# magicBoard.net
KiCad netlist of a schematic drawn in EAGLE
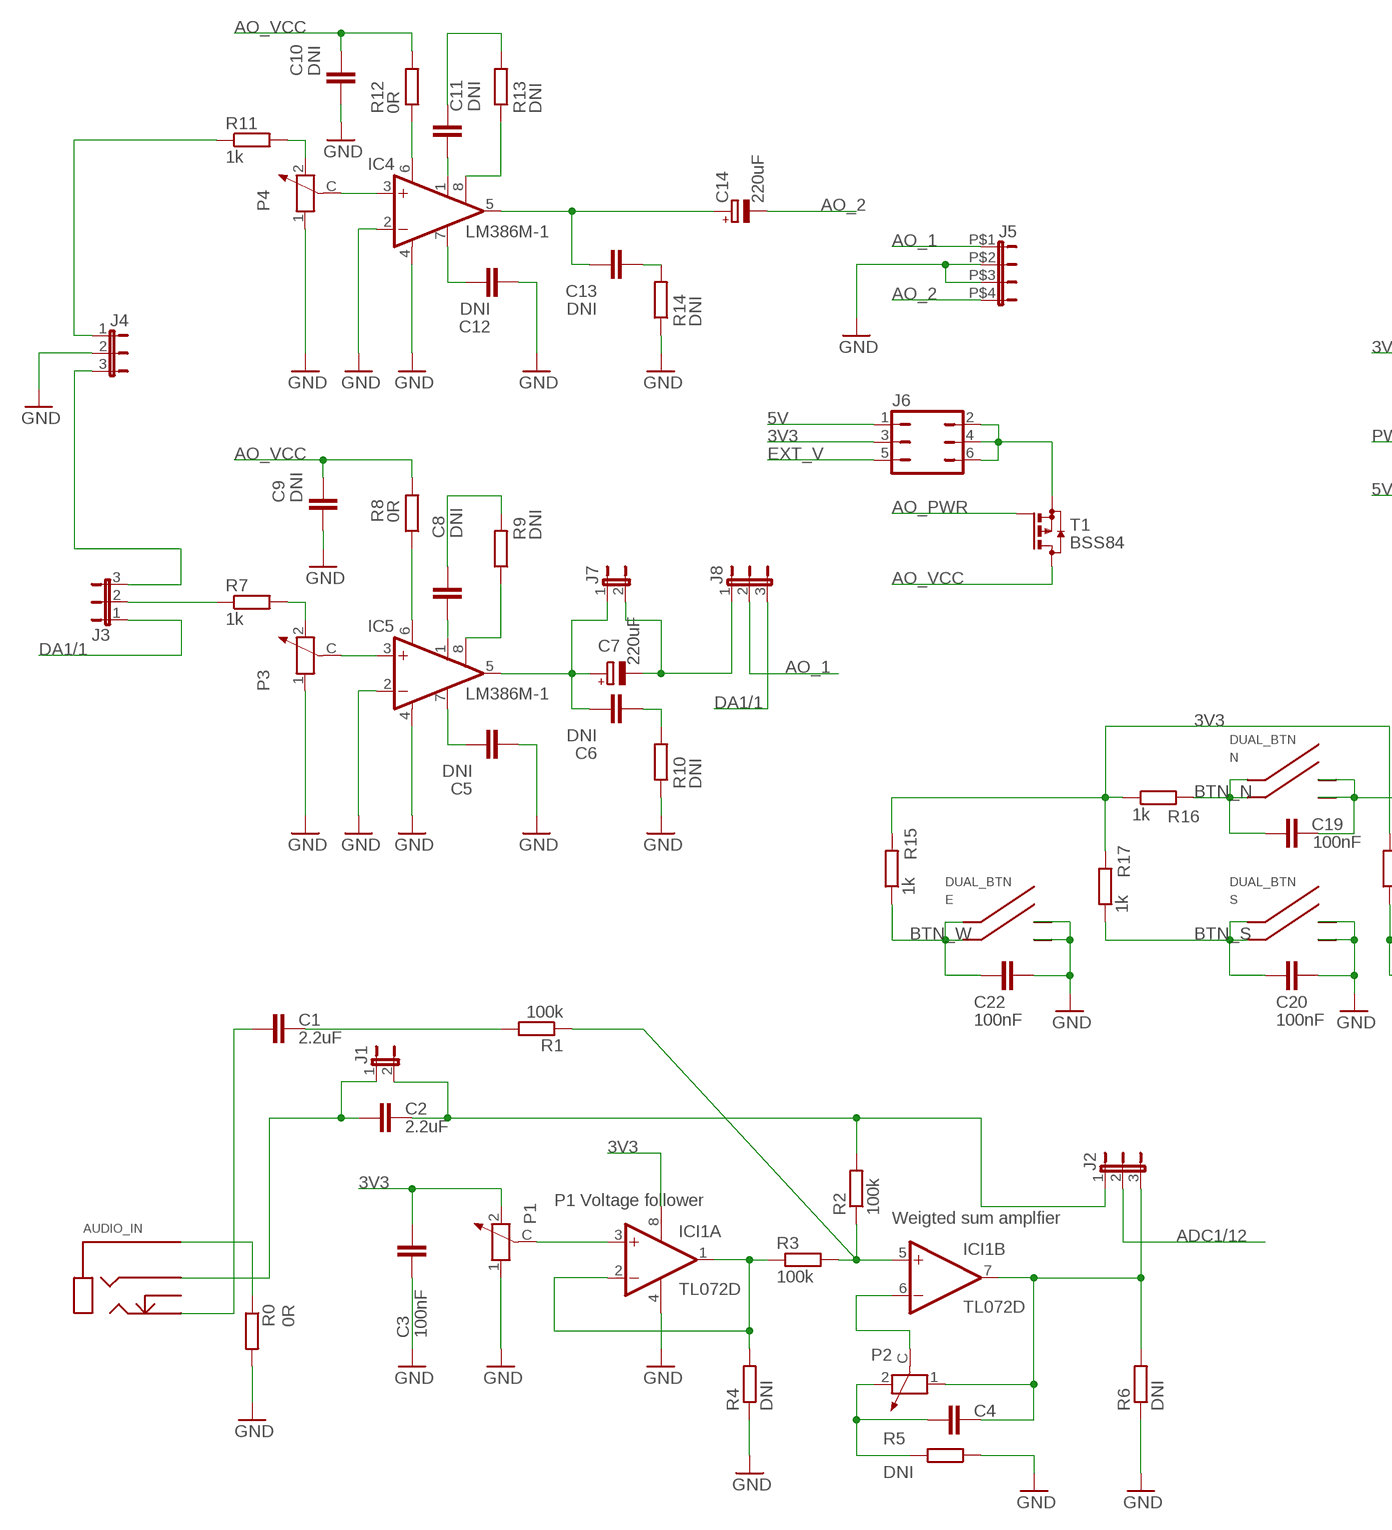
[diagram p0: schematic, sheet 1, part 1 of 2]
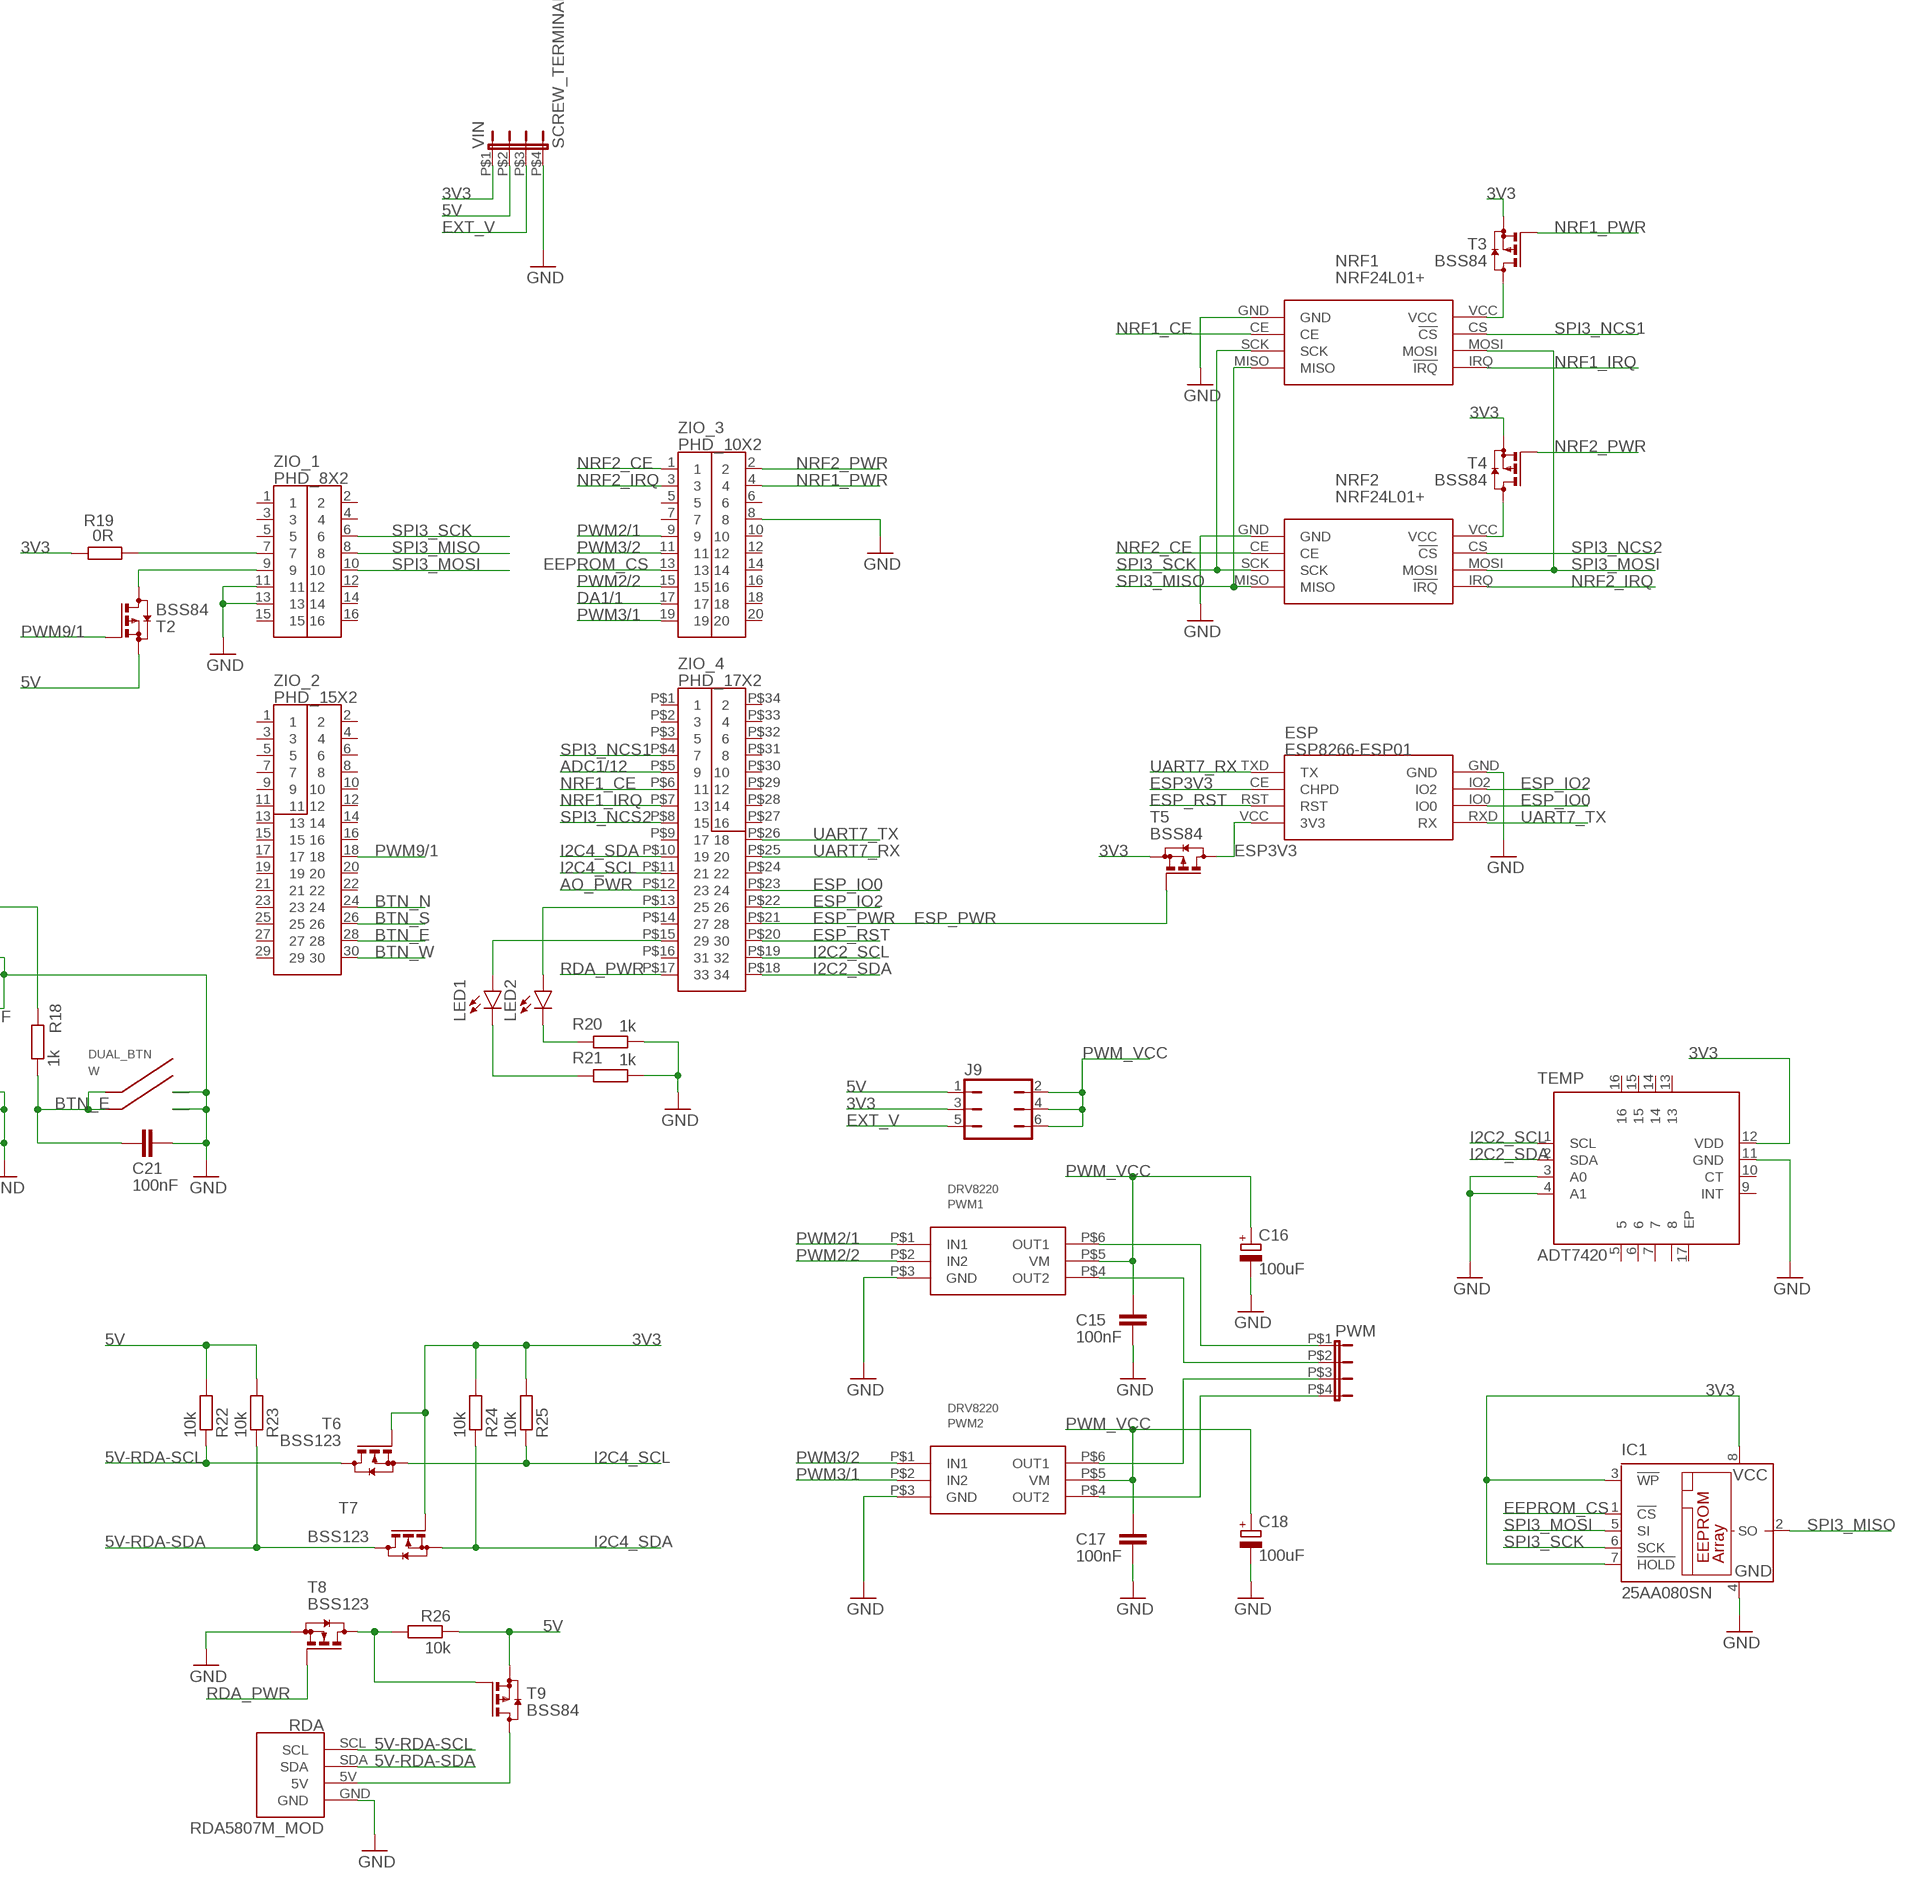
[diagram p1: schematic, sheet 1, part 2 of 2]

(export (version "E")
  (design (tool "Eeschema 10.0.6"))
  (components
    (comp (ref "AUDIO_IN")
      (value "CON_JACK")
      (footprint "eagle-import:CON_JACK")
      (libsource (lib "eagle-import") (part "CON_JACK"))
    )
    (comp (ref "C1")
      (value "2.2uF")
      (footprint "eagle-import:C0805")
      (libsource (lib "eagle-import") (part "C-EUC0805"))
    )
    (comp (ref "C2")
      (value "2.2uF")
      (footprint "eagle-import:C0805")
      (libsource (lib "eagle-import") (part "C-EUC0805"))
    )
    (comp (ref "C3")
      (value "100nF")
      (footprint "eagle-import:C0805")
      (libsource (lib "eagle-import") (part "C-EUC0805"))
    )
    (comp (ref "C4")
      (value "DNI")
      (footprint "eagle-import:C0805")
      (libsource (lib "eagle-import") (part "C-EUC0805"))
    )
    (comp (ref "C5")
      (value "DNI")
      (footprint "eagle-import:C0805")
      (libsource (lib "eagle-import") (part "C-EUC0805"))
    )
    (comp (ref "C6")
      (value "DNI")
      (footprint "eagle-import:C0805")
      (libsource (lib "eagle-import") (part "C-EUC0805"))
    )
    (comp (ref "C7")
      (value "220uF")
      (footprint "eagle-import:E2,5-6E")
      (libsource (lib "eagle-import") (part "CPOL-EUE2,5-6E"))
    )
    (comp (ref "C8")
      (value "DNI")
      (footprint "eagle-import:C0805")
      (libsource (lib "eagle-import") (part "C-EUC0805"))
    )
    (comp (ref "C9")
      (value "DNI")
      (footprint "eagle-import:C0805")
      (libsource (lib "eagle-import") (part "C-EUC0805"))
    )
    (comp (ref "C10")
      (value "DNI")
      (footprint "eagle-import:C0805")
      (libsource (lib "eagle-import") (part "C-EUC0805"))
    )
    (comp (ref "C11")
      (value "DNI")
      (footprint "eagle-import:C0805")
      (libsource (lib "eagle-import") (part "C-EUC0805"))
    )
    (comp (ref "C12")
      (value "DNI")
      (footprint "eagle-import:C0805")
      (libsource (lib "eagle-import") (part "C-EUC0805"))
    )
    (comp (ref "C13")
      (value "DNI")
      (footprint "eagle-import:C0805")
      (libsource (lib "eagle-import") (part "C-EUC0805"))
    )
    (comp (ref "C14")
      (value "220uF")
      (footprint "eagle-import:E2,5-6E")
      (libsource (lib "eagle-import") (part "CPOL-EUE2,5-6E"))
    )
    (comp (ref "C15")
      (value "100nF")
      (footprint "eagle-import:C0805")
      (libsource (lib "eagle-import") (part "C-EUC0805"))
    )
    (comp (ref "C16")
      (value "100uF")
      (footprint "eagle-import:E2,5-6E")
      (libsource (lib "eagle-import") (part "CPOL-EUE2,5-6E"))
    )
    (comp (ref "C17")
      (value "100nF")
      (footprint "eagle-import:C0805")
      (libsource (lib "eagle-import") (part "C-EUC0805"))
    )
    (comp (ref "C18")
      (value "100uF")
      (footprint "eagle-import:E2,5-6E")
      (libsource (lib "eagle-import") (part "CPOL-EUE2,5-6E"))
    )
    (comp (ref "C19")
      (value "100nF")
      (footprint "eagle-import:C0805")
      (libsource (lib "eagle-import") (part "C-EUC0805"))
    )
    (comp (ref "C20")
      (value "100nF")
      (footprint "eagle-import:C0805")
      (libsource (lib "eagle-import") (part "C-EUC0805"))
    )
    (comp (ref "C21")
      (value "100nF")
      (footprint "eagle-import:C0805")
      (libsource (lib "eagle-import") (part "C-EUC0805"))
    )
    (comp (ref "C22")
      (value "100nF")
      (footprint "eagle-import:C0805")
      (libsource (lib "eagle-import") (part "C-EUC0805"))
    )
    (comp (ref "E")
      (value "DUAL_BTN")
      (footprint "eagle-import:SMT_BTN")
      (libsource (lib "eagle-import") (part "DUAL_BTN"))
    )
    (comp (ref "ESP")
      (value "ESP8266-ESP01")
      (footprint "eagle-import:ESP8266-ESP01")
      (libsource (lib "eagle-import") (part "ESP8266-ESP01"))
    )
    (comp (ref "IC1")
      (value "25AA080SN")
      (footprint "eagle-import:SO-08")
      (fields (field (name "MF") "MICROCHIP") (field (name "MPN") "25AA080/SN"))
      (libsource (lib "eagle-import") (part "25SNAA080"))
    )
    (comp (ref "IC4")
      (value "LM386M-1")
      (footprint "eagle-import:SO08")
      (libsource (lib "eagle-import") (part "LM386?-M1"))
    )
    (comp (ref "IC5")
      (value "LM386M-1")
      (footprint "eagle-import:SO08")
      (libsource (lib "eagle-import") (part "LM386?-M1"))
    )
    (comp (ref "ICI1")
      (value "TL072D")
      (footprint "eagle-import:SO08")
      (libsource (lib "eagle-import") (part "TL072D"))
    )
    (comp (ref "J1")
      (value "JP1E")
      (footprint "eagle-import:JP1")
      (libsource (lib "eagle-import") (part "JP1E"))
    )
    (comp (ref "J2")
      (value "JP2E")
      (footprint "eagle-import:JP2")
      (libsource (lib "eagle-import") (part "JP2E"))
    )
    (comp (ref "J3")
      (value "JP2E")
      (footprint "eagle-import:JP2")
      (libsource (lib "eagle-import") (part "JP2E"))
    )
    (comp (ref "J4")
      (value "JP2E")
      (footprint "eagle-import:JP2")
      (libsource (lib "eagle-import") (part "JP2E"))
    )
    (comp (ref "J5")
      (value "SCREW_TERMINAL")
      (footprint "eagle-import:SCREW_TERMINAL")
      (libsource (lib "eagle-import") (part "SCREW_TERMINAL"))
    )
    (comp (ref "J6")
      (value "JP3Q")
      (footprint "eagle-import:JP3Q")
      (libsource (lib "eagle-import") (part "JP3Q"))
    )
    (comp (ref "J7")
      (value "JP1E")
      (footprint "eagle-import:JP1")
      (libsource (lib "eagle-import") (part "JP1E"))
    )
    (comp (ref "J8")
      (value "JP2E")
      (footprint "eagle-import:JP2")
      (libsource (lib "eagle-import") (part "JP2E"))
    )
    (comp (ref "J9")
      (value "JP3Q")
      (footprint "eagle-import:JP3Q")
      (libsource (lib "eagle-import") (part "JP3Q"))
    )
    (comp (ref "LED1")
      (value "LEDSMT1206")
      (footprint "eagle-import:1206")
      (libsource (lib "eagle-import") (part "LEDSMT1206"))
    )
    (comp (ref "LED2")
      (value "LEDSMT1206")
      (footprint "eagle-import:1206")
      (libsource (lib "eagle-import") (part "LEDSMT1206"))
    )
    (comp (ref "N")
      (value "DUAL_BTN")
      (footprint "eagle-import:SMT_BTN")
      (libsource (lib "eagle-import") (part "DUAL_BTN"))
    )
    (comp (ref "NRF1")
      (value "NRF24L01+")
      (footprint "eagle-import:NRF24L01+")
      (libsource (lib "eagle-import") (part "NRF24L01+"))
    )
    (comp (ref "NRF2")
      (value "NRF24L01+")
      (footprint "eagle-import:NRF24L01+")
      (libsource (lib "eagle-import") (part "NRF24L01+"))
    )
    (comp (ref "P1")
      (value "35W-POT")
      (footprint "eagle-import:35W_POT")
      (libsource (lib "eagle-import") (part "35W-POT"))
    )
    (comp (ref "P2")
      (value "35W-POT")
      (footprint "eagle-import:35W_POT")
      (libsource (lib "eagle-import") (part "35W-POT"))
    )
    (comp (ref "P3")
      (value "35W-POT")
      (footprint "eagle-import:35W_POT")
      (libsource (lib "eagle-import") (part "35W-POT"))
    )
    (comp (ref "P4")
      (value "35W-POT")
      (footprint "eagle-import:35W_POT")
      (libsource (lib "eagle-import") (part "35W-POT"))
    )
    (comp (ref "PWM")
      (value "SCREW_TERMINAL")
      (footprint "eagle-import:SCREW_TERMINAL")
      (libsource (lib "eagle-import") (part "SCREW_TERMINAL"))
    )
    (comp (ref "PWM1")
      (value "DRV8220")
      (footprint "eagle-import:SOT-5X3")
      (libsource (lib "eagle-import") (part "DRV8220"))
    )
    (comp (ref "PWM2")
      (value "DRV8220")
      (footprint "eagle-import:SOT-5X3")
      (libsource (lib "eagle-import") (part "DRV8220"))
    )
    (comp (ref "R0")
      (value "0R")
      (footprint "eagle-import:R0805")
      (libsource (lib "eagle-import") (part "R-EU_R0805"))
    )
    (comp (ref "R1")
      (value "100k")
      (footprint "eagle-import:R0805")
      (libsource (lib "eagle-import") (part "R-EU_R0805"))
    )
    (comp (ref "R2")
      (value "100k")
      (footprint "eagle-import:R0805")
      (libsource (lib "eagle-import") (part "R-EU_R0805"))
    )
    (comp (ref "R3")
      (value "100k")
      (footprint "eagle-import:R0805")
      (libsource (lib "eagle-import") (part "R-EU_R0805"))
    )
    (comp (ref "R4")
      (value "DNI")
      (footprint "eagle-import:R0805")
      (libsource (lib "eagle-import") (part "R-EU_R0805"))
    )
    (comp (ref "R5")
      (value "DNI")
      (footprint "eagle-import:R0805")
      (libsource (lib "eagle-import") (part "R-EU_R0805"))
    )
    (comp (ref "R6")
      (value "DNI")
      (footprint "eagle-import:R0805")
      (libsource (lib "eagle-import") (part "R-EU_R0805"))
    )
    (comp (ref "R7")
      (value "1k")
      (footprint "eagle-import:R0805")
      (libsource (lib "eagle-import") (part "R-EU_R0805"))
    )
    (comp (ref "R8")
      (value "0R")
      (footprint "eagle-import:R0805")
      (libsource (lib "eagle-import") (part "R-EU_R0805"))
    )
    (comp (ref "R9")
      (value "DNI")
      (footprint "eagle-import:R0805")
      (libsource (lib "eagle-import") (part "R-EU_R0805"))
    )
    (comp (ref "R10")
      (value "DNI")
      (footprint "eagle-import:R0805")
      (libsource (lib "eagle-import") (part "R-EU_R0805"))
    )
    (comp (ref "R11")
      (value "1k")
      (footprint "eagle-import:R0805")
      (libsource (lib "eagle-import") (part "R-EU_R0805"))
    )
    (comp (ref "R12")
      (value "0R")
      (footprint "eagle-import:R0805")
      (libsource (lib "eagle-import") (part "R-EU_R0805"))
    )
    (comp (ref "R13")
      (value "DNI")
      (footprint "eagle-import:R0805")
      (libsource (lib "eagle-import") (part "R-EU_R0805"))
    )
    (comp (ref "R14")
      (value "DNI")
      (footprint "eagle-import:R0805")
      (libsource (lib "eagle-import") (part "R-EU_R0805"))
    )
    (comp (ref "R15")
      (value "1k")
      (footprint "eagle-import:R0805")
      (libsource (lib "eagle-import") (part "R-EU_R0805"))
    )
    (comp (ref "R16")
      (value "1k")
      (footprint "eagle-import:R0805")
      (libsource (lib "eagle-import") (part "R-EU_R0805"))
    )
    (comp (ref "R17")
      (value "1k")
      (footprint "eagle-import:R0805")
      (libsource (lib "eagle-import") (part "R-EU_R0805"))
    )
    (comp (ref "R18")
      (value "1k")
      (footprint "eagle-import:R0805")
      (libsource (lib "eagle-import") (part "R-EU_R0805"))
    )
    (comp (ref "R19")
      (value "0R")
      (footprint "eagle-import:R0805")
      (libsource (lib "eagle-import") (part "R-EU_R0805"))
    )
    (comp (ref "R20")
      (value "1k")
      (footprint "eagle-import:R0805")
      (libsource (lib "eagle-import") (part "R-EU_R0805"))
    )
    (comp (ref "R21")
      (value "1k")
      (footprint "eagle-import:R0805")
      (libsource (lib "eagle-import") (part "R-EU_R0805"))
    )
    (comp (ref "R22")
      (value "10k")
      (footprint "eagle-import:R0805")
      (libsource (lib "eagle-import") (part "R-EU_R0805"))
    )
    (comp (ref "R23")
      (value "10k")
      (footprint "eagle-import:R0805")
      (libsource (lib "eagle-import") (part "R-EU_R0805"))
    )
    (comp (ref "R24")
      (value "10k")
      (footprint "eagle-import:R0805")
      (libsource (lib "eagle-import") (part "R-EU_R0805"))
    )
    (comp (ref "R25")
      (value "10k")
      (footprint "eagle-import:R0805")
      (libsource (lib "eagle-import") (part "R-EU_R0805"))
    )
    (comp (ref "R26")
      (value "10k")
      (footprint "eagle-import:R0805")
      (libsource (lib "eagle-import") (part "R-EU_R0805"))
    )
    (comp (ref "RDA")
      (value "RDA5807M_MOD")
      (footprint "eagle-import:RDA5807M")
      (libsource (lib "eagle-import") (part "RDA5807M_MOD"))
    )
    (comp (ref "S")
      (value "DUAL_BTN")
      (footprint "eagle-import:SMT_BTN")
      (libsource (lib "eagle-import") (part "DUAL_BTN"))
    )
    (comp (ref "T1")
      (value "BSS84")
      (footprint "eagle-import:SOT23")
      (libsource (lib "eagle-import") (part "BSS84"))
    )
    (comp (ref "T2")
      (value "BSS84")
      (footprint "eagle-import:SOT23")
      (libsource (lib "eagle-import") (part "BSS84"))
    )
    (comp (ref "T3")
      (value "BSS84")
      (footprint "eagle-import:SOT23")
      (libsource (lib "eagle-import") (part "BSS84"))
    )
    (comp (ref "T4")
      (value "BSS84")
      (footprint "eagle-import:SOT23")
      (libsource (lib "eagle-import") (part "BSS84"))
    )
    (comp (ref "T5")
      (value "BSS84")
      (footprint "eagle-import:SOT23")
      (libsource (lib "eagle-import") (part "BSS84"))
    )
    (comp (ref "T6")
      (value "BSS123")
      (footprint "eagle-import:SOT23")
      (libsource (lib "eagle-import") (part "BSS123"))
    )
    (comp (ref "T7")
      (value "BSS123")
      (footprint "eagle-import:SOT23")
      (libsource (lib "eagle-import") (part "BSS123"))
    )
    (comp (ref "T8")
      (value "BSS123")
      (footprint "eagle-import:SOT23")
      (libsource (lib "eagle-import") (part "BSS123"))
    )
    (comp (ref "T9")
      (value "BSS84")
      (footprint "eagle-import:SOT23")
      (libsource (lib "eagle-import") (part "BSS84"))
    )
    (comp (ref "TEMP")
      (value "ADT7420")
      (footprint "eagle-import:LFCSP-16")
      (libsource (lib "eagle-import") (part "ADT7420"))
    )
    (comp (ref "VIN")
      (value "SCREW_TERMINAL")
      (footprint "eagle-import:SCREW_TERMINAL")
      (libsource (lib "eagle-import") (part "SCREW_TERMINAL"))
    )
    (comp (ref "W")
      (value "DUAL_BTN")
      (footprint "eagle-import:SMT_BTN")
      (libsource (lib "eagle-import") (part "DUAL_BTN"))
    )
    (comp (ref "ZIO_1")
      (value "PHD_8X2")
      (footprint "eagle-import:PHD_8X2")
      (libsource (lib "eagle-import") (part "PHD_8X2"))
    )
    (comp (ref "ZIO_2")
      (value "PHD_15X2")
      (footprint "eagle-import:PHD_15X2")
      (libsource (lib "eagle-import") (part "PHD_15X2"))
    )
    (comp (ref "ZIO_3")
      (value "PHD_10X2")
      (footprint "eagle-import:PHD_10X2")
      (libsource (lib "eagle-import") (part "PHD_10X2"))
    )
    (comp (ref "ZIO_4")
      (value "PHD_17X2")
      (footprint "eagle-import:PHD_17X2")
      (libsource (lib "eagle-import") (part "PHD_17X2"))
    )
  )
  (nets
    (net (code "1") (name "/3V3") (class "Default")
      (node (ref "C3") (pin "1") (pinfunction "1_1") (pintype "passive"))
      (node (ref "IC1") (pin "3") (pinfunction "~{WP}_3") (pintype "input"))
      (node (ref "IC1") (pin "7") (pinfunction "~{HOLD}_7") (pintype "input"))
      (node (ref "IC1") (pin "8") (pinfunction "VCC_8") (pintype "power_in"))
      (node (ref "ICI1") (pin "8") (pinfunction "V+_8") (pintype "power_in"))
      (node (ref "J6") (pin "3") (pinfunction "3_3") (pintype "passive"))
      (node (ref "J9") (pin "3") (pinfunction "3_3") (pintype "passive"))
      (node (ref "P1") (pin "2") (pinfunction "2_2") (pintype "passive"))
      (node (ref "R15") (pin "2") (pinfunction "2_2") (pintype "passive"))
      (node (ref "R16") (pin "1") (pinfunction "1_1") (pintype "passive"))
      (node (ref "R17") (pin "2") (pinfunction "2_2") (pintype "passive"))
      (node (ref "R18") (pin "2") (pinfunction "2_2") (pintype "passive"))
      (node (ref "R19") (pin "2") (pinfunction "2_2") (pintype "passive"))
      (node (ref "R24") (pin "2") (pinfunction "2_2") (pintype "passive"))
      (node (ref "R25") (pin "2") (pinfunction "2_2") (pintype "passive"))
      (node (ref "T3") (pin "2") (pinfunction "S_2") (pintype "passive"))
      (node (ref "T4") (pin "2") (pinfunction "S_2") (pintype "passive"))
      (node (ref "T5") (pin "2") (pinfunction "S_2") (pintype "passive"))
      (node (ref "T6") (pin "1") (pinfunction "G_1") (pintype "passive"))
      (node (ref "T7") (pin "1") (pinfunction "G_1") (pintype "passive"))
      (node (ref "TEMP") (pin "12") (pinfunction "VDD_12") (pintype "input"))
      (node (ref "VIN") (pin "P$1") (pinfunction "1_P$1") (pintype "passive"))
    )
    (net (code "2") (name "/5V") (class "Default")
      (node (ref "J6") (pin "1") (pinfunction "1_1") (pintype "passive"))
      (node (ref "J9") (pin "1") (pinfunction "1_1") (pintype "passive"))
      (node (ref "R22") (pin "2") (pinfunction "2_2") (pintype "passive"))
      (node (ref "R23") (pin "2") (pinfunction "2_2") (pintype "passive"))
      (node (ref "R26") (pin "1") (pinfunction "1_1") (pintype "passive"))
      (node (ref "T2") (pin "2") (pinfunction "S_2") (pintype "passive"))
      (node (ref "T9") (pin "2") (pinfunction "S_2") (pintype "passive"))
      (node (ref "VIN") (pin "P$2") (pinfunction "2_P$2") (pintype "passive"))
    )
    (net (code "3") (name "/5V-RDA-SCL") (class "Default")
      (node (ref "R22") (pin "1") (pinfunction "1_1") (pintype "passive"))
      (node (ref "RDA") (pin "SCL") (pinfunction "SCL_SCL") (pintype "bidirectional"))
      (node (ref "T6") (pin "3") (pinfunction "D_3") (pintype "passive"))
    )
    (net (code "4") (name "/5V-RDA-SDA") (class "Default")
      (node (ref "R23") (pin "1") (pinfunction "1_1") (pintype "passive"))
      (node (ref "RDA") (pin "SDA") (pinfunction "SDA_SDA") (pintype "bidirectional"))
      (node (ref "T7") (pin "3") (pinfunction "D_3") (pintype "passive"))
    )
    (net (code "5") (name "/ADC1{slash}12") (class "Default")
      (node (ref "J2") (pin "2") (pinfunction "2_2") (pintype "passive"))
      (node (ref "ZIO_4") (pin "P$5") (pinfunction "9_P$5") (pintype "bidirectional"))
    )
    (net (code "6") (name "/AO_1") (class "Default")
      (node (ref "J5") (pin "P$1") (pinfunction "1_P$1") (pintype "passive"))
      (node (ref "J8") (pin "2") (pinfunction "2_2") (pintype "passive"))
    )
    (net (code "7") (name "/AO_2") (class "Default")
      (node (ref "C14") (pin "-") (pinfunction "-_-") (pintype "passive"))
      (node (ref "J5") (pin "P$4") (pinfunction "4_P$4") (pintype "passive"))
    )
    (net (code "8") (name "/AO_PWR") (class "Default")
      (node (ref "T1") (pin "1") (pinfunction "G_1") (pintype "passive"))
      (node (ref "ZIO_4") (pin "P$12") (pinfunction "23_P$12") (pintype "bidirectional"))
    )
    (net (code "9") (name "/AO_VCC") (class "Default")
      (node (ref "C10") (pin "1") (pinfunction "1_1") (pintype "passive"))
      (node (ref "C9") (pin "1") (pinfunction "1_1") (pintype "passive"))
      (node (ref "R12") (pin "2") (pinfunction "2_2") (pintype "passive"))
      (node (ref "R8") (pin "2") (pinfunction "2_2") (pintype "passive"))
      (node (ref "T1") (pin "3") (pinfunction "D_3") (pintype "passive"))
    )
    (net (code "10") (name "/BTN_E") (class "Default")
      (node (ref "C21") (pin "1") (pinfunction "1_1") (pintype "passive"))
      (node (ref "R18") (pin "1") (pinfunction "1_1") (pintype "passive"))
      (node (ref "W") (pin "H1") (pinfunction "L1_H1") (pintype "bidirectional"))
      (node (ref "W") (pin "H2") (pinfunction "L2_H2") (pintype "bidirectional"))
      (node (ref "ZIO_2") (pin "28") (pinfunction "28_28") (pintype "bidirectional"))
    )
    (net (code "11") (name "/BTN_N") (class "Default")
      (node (ref "C19") (pin "1") (pinfunction "1_1") (pintype "passive"))
      (node (ref "N") (pin "H1") (pinfunction "L1_H1") (pintype "bidirectional"))
      (node (ref "N") (pin "H2") (pinfunction "L2_H2") (pintype "bidirectional"))
      (node (ref "R16") (pin "2") (pinfunction "2_2") (pintype "passive"))
      (node (ref "ZIO_2") (pin "24") (pinfunction "24_24") (pintype "bidirectional"))
    )
    (net (code "12") (name "/BTN_S") (class "Default")
      (node (ref "C20") (pin "1") (pinfunction "1_1") (pintype "passive"))
      (node (ref "R17") (pin "1") (pinfunction "1_1") (pintype "passive"))
      (node (ref "S") (pin "H1") (pinfunction "L1_H1") (pintype "bidirectional"))
      (node (ref "S") (pin "H2") (pinfunction "L2_H2") (pintype "bidirectional"))
      (node (ref "ZIO_2") (pin "26") (pinfunction "26_26") (pintype "bidirectional"))
    )
    (net (code "13") (name "/BTN_W") (class "Default")
      (node (ref "C22") (pin "1") (pinfunction "1_1") (pintype "passive"))
      (node (ref "E") (pin "H1") (pinfunction "L1_H1") (pintype "bidirectional"))
      (node (ref "E") (pin "H2") (pinfunction "L2_H2") (pintype "bidirectional"))
      (node (ref "R15") (pin "1") (pinfunction "1_1") (pintype "passive"))
      (node (ref "ZIO_2") (pin "30") (pinfunction "30_30") (pintype "bidirectional"))
    )
    (net (code "14") (name "/DA1{slash}1") (class "Default")
      (node (ref "J3") (pin "1") (pinfunction "1_1") (pintype "passive"))
      (node (ref "J8") (pin "3") (pinfunction "3_3") (pintype "passive"))
      (node (ref "ZIO_3") (pin "17") (pinfunction "17_17") (pintype "bidirectional"))
    )
    (net (code "15") (name "/EEPROM_CS") (class "Default")
      (node (ref "IC1") (pin "1") (pinfunction "~{CS}_1") (pintype "input"))
      (node (ref "ZIO_3") (pin "13") (pinfunction "13_13") (pintype "bidirectional"))
    )
    (net (code "16") (name "/ESP3V3") (class "Default")
      (node (ref "ESP") (pin "CE") (pinfunction "CHPD_CE") (pintype "bidirectional"))
      (node (ref "ESP") (pin "VCC") (pinfunction "3V3_VCC") (pintype "bidirectional"))
      (node (ref "T5") (pin "3") (pinfunction "D_3") (pintype "passive"))
    )
    (net (code "17") (name "/ESP_IO0") (class "Default")
      (node (ref "ESP") (pin "IO0") (pinfunction "IO0_IO0") (pintype "bidirectional"))
      (node (ref "ZIO_4") (pin "P$23") (pinfunction "24_P$23") (pintype "bidirectional"))
    )
    (net (code "18") (name "/ESP_IO2") (class "Default")
      (node (ref "ESP") (pin "IO2") (pinfunction "IO2_IO2") (pintype "bidirectional"))
      (node (ref "ZIO_4") (pin "P$22") (pinfunction "26_P$22") (pintype "bidirectional"))
    )
    (net (code "19") (name "/ESP_PWR") (class "Default")
      (node (ref "T5") (pin "1") (pinfunction "G_1") (pintype "passive"))
      (node (ref "ZIO_4") (pin "P$21") (pinfunction "28_P$21") (pintype "bidirectional"))
    )
    (net (code "20") (name "/ESP_RST") (class "Default")
      (node (ref "ESP") (pin "RST") (pinfunction "RST_RST") (pintype "bidirectional"))
      (node (ref "ZIO_4") (pin "P$20") (pinfunction "30_P$20") (pintype "bidirectional"))
    )
    (net (code "21") (name "/EXT_V") (class "Default")
      (node (ref "J6") (pin "5") (pinfunction "5_5") (pintype "passive"))
      (node (ref "J9") (pin "5") (pinfunction "5_5") (pintype "passive"))
      (node (ref "VIN") (pin "P$3") (pinfunction "3_P$3") (pintype "passive"))
    )
    (net (code "22") (name "/I2C2_SCL") (class "Default")
      (node (ref "TEMP") (pin "1") (pinfunction "SCL_1") (pintype "input"))
      (node (ref "ZIO_4") (pin "P$19") (pinfunction "32_P$19") (pintype "bidirectional"))
    )
    (net (code "23") (name "/I2C2_SDA") (class "Default")
      (node (ref "TEMP") (pin "2") (pinfunction "SDA_2") (pintype "input"))
      (node (ref "ZIO_4") (pin "P$18") (pinfunction "34_P$18") (pintype "bidirectional"))
    )
    (net (code "24") (name "/I2C4_SCL") (class "Default")
      (node (ref "R25") (pin "1") (pinfunction "1_1") (pintype "passive"))
      (node (ref "T6") (pin "2") (pinfunction "S_2") (pintype "passive"))
      (node (ref "ZIO_4") (pin "P$11") (pinfunction "21_P$11") (pintype "bidirectional"))
    )
    (net (code "25") (name "/I2C4_SDA") (class "Default")
      (node (ref "R24") (pin "1") (pinfunction "1_1") (pintype "passive"))
      (node (ref "T7") (pin "2") (pinfunction "S_2") (pintype "passive"))
      (node (ref "ZIO_4") (pin "P$10") (pinfunction "19_P$10") (pintype "bidirectional"))
    )
    (net (code "26") (name "/NRF1_CE") (class "Default")
      (node (ref "NRF1") (pin "CE") (pinfunction "CE_CE") (pintype "bidirectional"))
      (node (ref "ZIO_4") (pin "P$6") (pinfunction "11_P$6") (pintype "bidirectional"))
    )
    (net (code "27") (name "/NRF1_IRQ") (class "Default")
      (node (ref "NRF1") (pin "IRQ") (pinfunction "~{IRQ}_IRQ") (pintype "bidirectional"))
      (node (ref "ZIO_4") (pin "P$7") (pinfunction "13_P$7") (pintype "bidirectional"))
    )
    (net (code "28") (name "/NRF1_PWR") (class "Default")
      (node (ref "T3") (pin "1") (pinfunction "G_1") (pintype "passive"))
      (node (ref "ZIO_3") (pin "4") (pinfunction "4_4") (pintype "bidirectional"))
    )
    (net (code "29") (name "/NRF2_CE") (class "Default")
      (node (ref "NRF2") (pin "CE") (pinfunction "CE_CE") (pintype "bidirectional"))
      (node (ref "ZIO_3") (pin "1") (pinfunction "1_1") (pintype "bidirectional"))
    )
    (net (code "30") (name "/NRF2_IRQ") (class "Default")
      (node (ref "NRF2") (pin "IRQ") (pinfunction "~{IRQ}_IRQ") (pintype "bidirectional"))
      (node (ref "ZIO_3") (pin "3") (pinfunction "3_3") (pintype "bidirectional"))
    )
    (net (code "31") (name "/NRF2_PWR") (class "Default")
      (node (ref "T4") (pin "1") (pinfunction "G_1") (pintype "passive"))
      (node (ref "ZIO_3") (pin "2") (pinfunction "2_2") (pintype "bidirectional"))
    )
    (net (code "32") (name "/PWM2{slash}1") (class "Default")
      (node (ref "PWM1") (pin "P$1") (pinfunction "IN1_P$1") (pintype "bidirectional"))
      (node (ref "ZIO_3") (pin "9") (pinfunction "9_9") (pintype "bidirectional"))
    )
    (net (code "33") (name "/PWM2{slash}2") (class "Default")
      (node (ref "PWM1") (pin "P$2") (pinfunction "IN2_P$2") (pintype "bidirectional"))
      (node (ref "ZIO_3") (pin "15") (pinfunction "15_15") (pintype "bidirectional"))
    )
    (net (code "34") (name "/PWM3{slash}1") (class "Default")
      (node (ref "PWM2") (pin "P$2") (pinfunction "IN2_P$2") (pintype "bidirectional"))
      (node (ref "ZIO_3") (pin "19") (pinfunction "19_19") (pintype "bidirectional"))
    )
    (net (code "35") (name "/PWM3{slash}2") (class "Default")
      (node (ref "PWM2") (pin "P$1") (pinfunction "IN1_P$1") (pintype "bidirectional"))
      (node (ref "ZIO_3") (pin "11") (pinfunction "11_11") (pintype "bidirectional"))
    )
    (net (code "36") (name "/PWM9{slash}1") (class "Default")
      (node (ref "T2") (pin "1") (pinfunction "G_1") (pintype "passive"))
      (node (ref "ZIO_2") (pin "18") (pinfunction "18_18") (pintype "bidirectional"))
    )
    (net (code "37") (name "/PWM_VCC") (class "Default")
      (node (ref "C15") (pin "1") (pinfunction "1_1") (pintype "passive"))
      (node (ref "C16") (pin "+") (pinfunction "+_+") (pintype "passive"))
      (node (ref "C17") (pin "1") (pinfunction "1_1") (pintype "passive"))
      (node (ref "C18") (pin "+") (pinfunction "+_+") (pintype "passive"))
      (node (ref "J9") (pin "2") (pinfunction "2_2") (pintype "passive"))
      (node (ref "J9") (pin "4") (pinfunction "4_4") (pintype "passive"))
      (node (ref "J9") (pin "6") (pinfunction "6_6") (pintype "passive"))
      (node (ref "PWM1") (pin "P$5") (pinfunction "VM_P$5") (pintype "bidirectional"))
      (node (ref "PWM2") (pin "P$5") (pinfunction "VM_P$5") (pintype "bidirectional"))
    )
    (net (code "38") (name "/RDA_PWR") (class "Default")
      (node (ref "T8") (pin "1") (pinfunction "G_1") (pintype "passive"))
      (node (ref "ZIO_4") (pin "P$17") (pinfunction "33_P$17") (pintype "bidirectional"))
    )
    (net (code "39") (name "/SPI3_MISO") (class "Default")
      (node (ref "IC1") (pin "2") (pinfunction "SO_2") (pintype "bidirectional"))
      (node (ref "NRF1") (pin "MISO") (pinfunction "MISO_MISO") (pintype "bidirectional"))
      (node (ref "NRF2") (pin "MISO") (pinfunction "MISO_MISO") (pintype "bidirectional"))
      (node (ref "ZIO_1") (pin "8") (pinfunction "8_8") (pintype "bidirectional"))
    )
    (net (code "40") (name "/SPI3_MOSI") (class "Default")
      (node (ref "IC1") (pin "5") (pinfunction "SI_5") (pintype "input"))
      (node (ref "NRF1") (pin "MOSI") (pinfunction "MOSI_MOSI") (pintype "bidirectional"))
      (node (ref "NRF2") (pin "MOSI") (pinfunction "MOSI_MOSI") (pintype "bidirectional"))
      (node (ref "ZIO_1") (pin "10") (pinfunction "10_10") (pintype "bidirectional"))
    )
    (net (code "41") (name "/SPI3_NCS1") (class "Default")
      (node (ref "NRF1") (pin "CS") (pinfunction "~{CS}_CS") (pintype "bidirectional"))
      (node (ref "ZIO_4") (pin "P$4") (pinfunction "7_P$4") (pintype "bidirectional"))
    )
    (net (code "42") (name "/SPI3_NCS2") (class "Default")
      (node (ref "NRF2") (pin "CS") (pinfunction "~{CS}_CS") (pintype "bidirectional"))
      (node (ref "ZIO_4") (pin "P$8") (pinfunction "15_P$8") (pintype "bidirectional"))
    )
    (net (code "43") (name "/SPI3_SCK") (class "Default")
      (node (ref "IC1") (pin "6") (pinfunction "SCK_6") (pintype "input"))
      (node (ref "NRF1") (pin "SCK") (pinfunction "SCK_SCK") (pintype "bidirectional"))
      (node (ref "NRF2") (pin "SCK") (pinfunction "SCK_SCK") (pintype "bidirectional"))
      (node (ref "ZIO_1") (pin "6") (pinfunction "6_6") (pintype "bidirectional"))
    )
    (net (code "44") (name "/UART7_RX") (class "Default")
      (node (ref "ESP") (pin "TXD") (pinfunction "TX_TXD") (pintype "bidirectional"))
      (node (ref "ZIO_4") (pin "P$25") (pinfunction "20_P$25") (pintype "bidirectional"))
    )
    (net (code "45") (name "/UART7_TX") (class "Default")
      (node (ref "ESP") (pin "RXD") (pinfunction "RX_RXD") (pintype "bidirectional"))
      (node (ref "ZIO_4") (pin "P$26") (pinfunction "18_P$26") (pintype "bidirectional"))
    )
    (net (code "46") (name "GND") (class "Default")
      (node (ref "C10") (pin "2") (pinfunction "2_2") (pintype "passive"))
      (node (ref "C12") (pin "2") (pinfunction "2_2") (pintype "passive"))
      (node (ref "C15") (pin "2") (pinfunction "2_2") (pintype "passive"))
      (node (ref "C16") (pin "-") (pinfunction "-_-") (pintype "passive"))
      (node (ref "C17") (pin "2") (pinfunction "2_2") (pintype "passive"))
      (node (ref "C18") (pin "-") (pinfunction "-_-") (pintype "passive"))
      (node (ref "C19") (pin "2") (pinfunction "2_2") (pintype "passive"))
      (node (ref "C20") (pin "2") (pinfunction "2_2") (pintype "passive"))
      (node (ref "C21") (pin "2") (pinfunction "2_2") (pintype "passive"))
      (node (ref "C22") (pin "2") (pinfunction "2_2") (pintype "passive"))
      (node (ref "C3") (pin "2") (pinfunction "2_2") (pintype "passive"))
      (node (ref "C5") (pin "2") (pinfunction "2_2") (pintype "passive"))
      (node (ref "C9") (pin "2") (pinfunction "2_2") (pintype "passive"))
      (node (ref "E") (pin "L1") (pinfunction "R1_L1") (pintype "bidirectional"))
      (node (ref "E") (pin "L2") (pinfunction "R2_L2") (pintype "bidirectional"))
      (node (ref "ESP") (pin "GND") (pinfunction "GND_GND") (pintype "bidirectional"))
      (node (ref "IC1") (pin "4") (pinfunction "GND_4") (pintype "power_in"))
      (node (ref "IC4") (pin "2") (pinfunction "-IN_2") (pintype "input"))
      (node (ref "IC4") (pin "4") (pinfunction "GND_4") (pintype "power_in"))
      (node (ref "IC5") (pin "2") (pinfunction "-IN_2") (pintype "input"))
      (node (ref "IC5") (pin "4") (pinfunction "GND_4") (pintype "power_in"))
      (node (ref "ICI1") (pin "4") (pinfunction "V-_4") (pintype "power_in"))
      (node (ref "J4") (pin "2") (pinfunction "2_2") (pintype "passive"))
      (node (ref "J5") (pin "P$2") (pinfunction "2_P$2") (pintype "passive"))
      (node (ref "J5") (pin "P$3") (pinfunction "3_P$3") (pintype "passive"))
      (node (ref "N") (pin "L1") (pinfunction "R1_L1") (pintype "bidirectional"))
      (node (ref "N") (pin "L2") (pinfunction "R2_L2") (pintype "bidirectional"))
      (node (ref "NRF1") (pin "GND") (pinfunction "GND_GND") (pintype "bidirectional"))
      (node (ref "NRF2") (pin "GND") (pinfunction "GND_GND") (pintype "bidirectional"))
      (node (ref "P1") (pin "1") (pinfunction "1_1") (pintype "passive"))
      (node (ref "P3") (pin "1") (pinfunction "1_1") (pintype "passive"))
      (node (ref "P4") (pin "1") (pinfunction "1_1") (pintype "passive"))
      (node (ref "PWM1") (pin "P$3") (pinfunction "GND_P$3") (pintype "bidirectional"))
      (node (ref "PWM2") (pin "P$3") (pinfunction "GND_P$3") (pintype "bidirectional"))
      (node (ref "R0") (pin "2") (pinfunction "2_2") (pintype "passive"))
      (node (ref "R10") (pin "1") (pinfunction "1_1") (pintype "passive"))
      (node (ref "R14") (pin "1") (pinfunction "1_1") (pintype "passive"))
      (node (ref "R20") (pin "1") (pinfunction "1_1") (pintype "passive"))
      (node (ref "R21") (pin "1") (pinfunction "1_1") (pintype "passive"))
      (node (ref "R4") (pin "1") (pinfunction "1_1") (pintype "passive"))
      (node (ref "R5") (pin "1") (pinfunction "1_1") (pintype "passive"))
      (node (ref "R6") (pin "1") (pinfunction "1_1") (pintype "passive"))
      (node (ref "RDA") (pin "GND") (pinfunction "GND_GND") (pintype "bidirectional"))
      (node (ref "S") (pin "L1") (pinfunction "R1_L1") (pintype "bidirectional"))
      (node (ref "S") (pin "L2") (pinfunction "R2_L2") (pintype "bidirectional"))
      (node (ref "T8") (pin "2") (pinfunction "S_2") (pintype "passive"))
      (node (ref "TEMP") (pin "11") (pinfunction "GND_11") (pintype "input"))
      (node (ref "TEMP") (pin "3") (pinfunction "A0_3") (pintype "input"))
      (node (ref "TEMP") (pin "4") (pinfunction "A1_4") (pintype "input"))
      (node (ref "VIN") (pin "P$4") (pinfunction "4_P$4") (pintype "passive"))
      (node (ref "W") (pin "L1") (pinfunction "R1_L1") (pintype "bidirectional"))
      (node (ref "W") (pin "L2") (pinfunction "R2_L2") (pintype "bidirectional"))
      (node (ref "ZIO_1") (pin "11") (pinfunction "11_11") (pintype "bidirectional"))
      (node (ref "ZIO_1") (pin "13") (pinfunction "13_13") (pintype "bidirectional"))
      (node (ref "ZIO_3") (pin "8") (pinfunction "8_8") (pintype "bidirectional"))
    )
    (net (code "47") (name "Net-(AUDIO_IN-3)") (class "Default")
      (node (ref "AUDIO_IN") (pin "2") (pinfunction "3_2") (pintype "bidirectional"))
      (node (ref "C2") (pin "2") (pinfunction "2_2") (pintype "passive"))
      (node (ref "J1") (pin "1") (pinfunction "1_1") (pintype "passive"))
    )
    (net (code "48") (name "Net-(AUDIO_IN-5)") (class "Default")
      (node (ref "AUDIO_IN") (pin "4") (pinfunction "5_4") (pintype "bidirectional"))
      (node (ref "C1") (pin "2") (pinfunction "2_2") (pintype "passive"))
    )
    (net (code "49") (name "Net-(AUDIO_IN-Pad1)") (class "Default")
      (node (ref "AUDIO_IN") (pin "1") (pinfunction "1_1") (pintype "bidirectional"))
      (node (ref "R0") (pin "1") (pinfunction "1_1") (pintype "passive"))
    )
    (net (code "50") (name "Net-(C1-Pad1)") (class "Default")
      (node (ref "C1") (pin "1") (pinfunction "1_1") (pintype "passive"))
      (node (ref "R1") (pin "2") (pinfunction "2_2") (pintype "passive"))
    )
    (net (code "51") (name "Net-(C2-Pad1)") (class "Default")
      (node (ref "C2") (pin "1") (pinfunction "1_1") (pintype "passive"))
      (node (ref "J1") (pin "2") (pinfunction "2_2") (pintype "passive"))
      (node (ref "J2") (pin "1") (pinfunction "1_1") (pintype "passive"))
      (node (ref "R2") (pin "2") (pinfunction "2_2") (pintype "passive"))
    )
    (net (code "52") (name "Net-(C4-Pad2)") (class "Default")
      (node (ref "C4") (pin "2") (pinfunction "2_2") (pintype "passive"))
      (node (ref "P2") (pin "2") (pinfunction "2_2") (pintype "passive"))
      (node (ref "R5") (pin "2") (pinfunction "2_2") (pintype "passive"))
    )
    (net (code "53") (name "Net-(C6-Pad2)") (class "Default")
      (node (ref "C6") (pin "2") (pinfunction "2_2") (pintype "passive"))
      (node (ref "R10") (pin "2") (pinfunction "2_2") (pintype "passive"))
    )
    (net (code "54") (name "Net-(C7-Pad-)") (class "Default")
      (node (ref "C7") (pin "-") (pinfunction "-_-") (pintype "passive"))
      (node (ref "J7") (pin "2") (pinfunction "2_2") (pintype "passive"))
      (node (ref "J8") (pin "1") (pinfunction "1_1") (pintype "passive"))
    )
    (net (code "55") (name "Net-(C8-Pad1)") (class "Default")
      (node (ref "C8") (pin "1") (pinfunction "1_1") (pintype "passive"))
      (node (ref "R9") (pin "2") (pinfunction "2_2") (pintype "passive"))
    )
    (net (code "56") (name "Net-(C8-Pad2)") (class "Default")
      (node (ref "C8") (pin "2") (pinfunction "2_2") (pintype "passive"))
      (node (ref "IC5") (pin "1") (pinfunction "GAIN_1") (pintype "passive"))
    )
    (net (code "57") (name "Net-(C11-Pad1)") (class "Default")
      (node (ref "C11") (pin "1") (pinfunction "1_1") (pintype "passive"))
      (node (ref "R13") (pin "2") (pinfunction "2_2") (pintype "passive"))
    )
    (net (code "58") (name "Net-(C11-Pad2)") (class "Default")
      (node (ref "C11") (pin "2") (pinfunction "2_2") (pintype "passive"))
      (node (ref "IC4") (pin "1") (pinfunction "GAIN_1") (pintype "passive"))
    )
    (net (code "59") (name "Net-(C13-Pad2)") (class "Default")
      (node (ref "C13") (pin "2") (pinfunction "2_2") (pintype "passive"))
      (node (ref "R14") (pin "2") (pinfunction "2_2") (pintype "passive"))
    )
    (net (code "60") (name "Net-(IC4-+IN)") (class "Default")
      (node (ref "IC4") (pin "3") (pinfunction "+IN_3") (pintype "input"))
      (node (ref "P4") (pin "C") (pinfunction "3_C") (pintype "passive"))
    )
    (net (code "61") (name "Net-(IC4-BYPASS)") (class "Default")
      (node (ref "C12") (pin "1") (pinfunction "1_1") (pintype "passive"))
      (node (ref "IC4") (pin "7") (pinfunction "BYPASS_7") (pintype "passive"))
    )
    (net (code "62") (name "Net-(IC4-GAIN-Pad8)") (class "Default")
      (node (ref "IC4") (pin "8") (pinfunction "GAIN_8") (pintype "passive"))
      (node (ref "R13") (pin "1") (pinfunction "1_1") (pintype "passive"))
    )
    (net (code "63") (name "Net-(IC4-OUT)") (class "Default")
      (node (ref "C13") (pin "1") (pinfunction "1_1") (pintype "passive"))
      (node (ref "C14") (pin "+") (pinfunction "+_+") (pintype "passive"))
      (node (ref "IC4") (pin "5") (pinfunction "OUT_5") (pintype "output"))
    )
    (net (code "64") (name "Net-(IC4-VS)") (class "Default")
      (node (ref "IC4") (pin "6") (pinfunction "VS_6") (pintype "power_in"))
      (node (ref "R12") (pin "1") (pinfunction "1_1") (pintype "passive"))
    )
    (net (code "65") (name "Net-(IC5-+IN)") (class "Default")
      (node (ref "IC5") (pin "3") (pinfunction "+IN_3") (pintype "input"))
      (node (ref "P3") (pin "C") (pinfunction "3_C") (pintype "passive"))
    )
    (net (code "66") (name "Net-(IC5-BYPASS)") (class "Default")
      (node (ref "C5") (pin "1") (pinfunction "1_1") (pintype "passive"))
      (node (ref "IC5") (pin "7") (pinfunction "BYPASS_7") (pintype "passive"))
    )
    (net (code "67") (name "Net-(IC5-GAIN-Pad8)") (class "Default")
      (node (ref "IC5") (pin "8") (pinfunction "GAIN_8") (pintype "passive"))
      (node (ref "R9") (pin "1") (pinfunction "1_1") (pintype "passive"))
    )
    (net (code "68") (name "Net-(IC5-OUT)") (class "Default")
      (node (ref "C6") (pin "1") (pinfunction "1_1") (pintype "passive"))
      (node (ref "C7") (pin "+") (pinfunction "+_+") (pintype "passive"))
      (node (ref "IC5") (pin "5") (pinfunction "OUT_5") (pintype "output"))
      (node (ref "J7") (pin "1") (pinfunction "1_1") (pintype "passive"))
    )
    (net (code "69") (name "Net-(IC5-VS)") (class "Default")
      (node (ref "IC5") (pin "6") (pinfunction "VS_6") (pintype "power_in"))
      (node (ref "R8") (pin "1") (pinfunction "1_1") (pintype "passive"))
    )
    (net (code "70") (name "Net-(ICI1A-+IN)") (class "Default")
      (node (ref "ICI1") (pin "3") (pinfunction "+IN_3") (pintype "input"))
      (node (ref "P1") (pin "C") (pinfunction "3_C") (pintype "passive"))
    )
    (net (code "71") (name "Net-(ICI1A--IN)") (class "Default")
      (node (ref "ICI1") (pin "1") (pinfunction "OUT_1") (pintype "output"))
      (node (ref "ICI1") (pin "2") (pinfunction "-IN_2") (pintype "input"))
      (node (ref "R3") (pin "1") (pinfunction "1_1") (pintype "passive"))
      (node (ref "R4") (pin "2") (pinfunction "2_2") (pintype "passive"))
    )
    (net (code "72") (name "Net-(ICI1B-+IN)") (class "Default")
      (node (ref "ICI1") (pin "5") (pinfunction "+IN_5") (pintype "input"))
      (node (ref "R1") (pin "1") (pinfunction "1_1") (pintype "passive"))
      (node (ref "R2") (pin "1") (pinfunction "1_1") (pintype "passive"))
      (node (ref "R3") (pin "2") (pinfunction "2_2") (pintype "passive"))
    )
    (net (code "73") (name "Net-(ICI1B--IN)") (class "Default")
      (node (ref "ICI1") (pin "6") (pinfunction "-IN_6") (pintype "input"))
      (node (ref "P2") (pin "C") (pinfunction "3_C") (pintype "passive"))
    )
    (net (code "74") (name "Net-(ICI1B-OUT)") (class "Default")
      (node (ref "C4") (pin "1") (pinfunction "1_1") (pintype "passive"))
      (node (ref "ICI1") (pin "7") (pinfunction "OUT_7") (pintype "output"))
      (node (ref "J2") (pin "3") (pinfunction "3_3") (pintype "passive"))
      (node (ref "P2") (pin "1") (pinfunction "1_1") (pintype "passive"))
      (node (ref "R6") (pin "2") (pinfunction "2_2") (pintype "passive"))
    )
    (net (code "75") (name "Net-(J3-Pad2)") (class "Default")
      (node (ref "J3") (pin "2") (pinfunction "2_2") (pintype "passive"))
      (node (ref "R7") (pin "1") (pinfunction "1_1") (pintype "passive"))
    )
    (net (code "76") (name "Net-(J3-Pad3)") (class "Default")
      (node (ref "J3") (pin "3") (pinfunction "3_3") (pintype "passive"))
      (node (ref "J4") (pin "3") (pinfunction "3_3") (pintype "passive"))
    )
    (net (code "77") (name "Net-(J4-Pad1)") (class "Default")
      (node (ref "J4") (pin "1") (pinfunction "1_1") (pintype "passive"))
      (node (ref "R11") (pin "1") (pinfunction "1_1") (pintype "passive"))
    )
    (net (code "78") (name "Net-(LED1-PadC)") (class "Default")
      (node (ref "LED1") (pin "C") (pinfunction "C_C") (pintype "passive"))
      (node (ref "R21") (pin "2") (pinfunction "2_2") (pintype "passive"))
    )
    (net (code "79") (name "Net-(LED2-PadC)") (class "Default")
      (node (ref "LED2") (pin "C") (pinfunction "C_C") (pintype "passive"))
      (node (ref "R20") (pin "2") (pinfunction "2_2") (pintype "passive"))
    )
    (net (code "80") (name "Net-(P3-Pad2)") (class "Default")
      (node (ref "P3") (pin "2") (pinfunction "2_2") (pintype "passive"))
      (node (ref "R7") (pin "2") (pinfunction "2_2") (pintype "passive"))
    )
    (net (code "81") (name "Net-(P4-Pad2)") (class "Default")
      (node (ref "P4") (pin "2") (pinfunction "2_2") (pintype "passive"))
      (node (ref "R11") (pin "2") (pinfunction "2_2") (pintype "passive"))
    )
    (net (code "82") (name "Net-(PWM-1)") (class "Default")
      (node (ref "PWM") (pin "P$1") (pinfunction "1_P$1") (pintype "passive"))
      (node (ref "PWM1") (pin "P$6") (pinfunction "OUT1_P$6") (pintype "bidirectional"))
    )
    (net (code "83") (name "Net-(PWM-2)") (class "Default")
      (node (ref "PWM") (pin "P$2") (pinfunction "2_P$2") (pintype "passive"))
      (node (ref "PWM1") (pin "P$4") (pinfunction "OUT2_P$4") (pintype "bidirectional"))
    )
    (net (code "84") (name "Net-(PWM-3)") (class "Default")
      (node (ref "PWM") (pin "P$3") (pinfunction "3_P$3") (pintype "passive"))
      (node (ref "PWM2") (pin "P$6") (pinfunction "OUT1_P$6") (pintype "bidirectional"))
    )
    (net (code "85") (name "Net-(PWM-4)") (class "Default")
      (node (ref "PWM") (pin "P$4") (pinfunction "4_P$4") (pintype "passive"))
      (node (ref "PWM2") (pin "P$4") (pinfunction "OUT2_P$4") (pintype "bidirectional"))
    )
    (net (code "86") (name "Net-(R19-Pad1)") (class "Default")
      (node (ref "R19") (pin "1") (pinfunction "1_1") (pintype "passive"))
      (node (ref "ZIO_1") (pin "7") (pinfunction "7_7") (pintype "bidirectional"))
    )
    (net (code "87") (name "Net-(T1-S)") (class "Default")
      (node (ref "J6") (pin "2") (pinfunction "2_2") (pintype "passive"))
      (node (ref "J6") (pin "4") (pinfunction "4_4") (pintype "passive"))
      (node (ref "J6") (pin "6") (pinfunction "6_6") (pintype "passive"))
      (node (ref "T1") (pin "2") (pinfunction "S_2") (pintype "passive"))
    )
    (net (code "88") (name "Net-(T2-D)") (class "Default")
      (node (ref "T2") (pin "3") (pinfunction "D_3") (pintype "passive"))
      (node (ref "ZIO_1") (pin "9") (pinfunction "9_9") (pintype "bidirectional"))
    )
    (net (code "89") (name "Net-(T3-D)") (class "Default")
      (node (ref "NRF1") (pin "VCC") (pinfunction "VCC_VCC") (pintype "bidirectional"))
      (node (ref "T3") (pin "3") (pinfunction "D_3") (pintype "passive"))
    )
    (net (code "90") (name "Net-(T4-D)") (class "Default")
      (node (ref "NRF2") (pin "VCC") (pinfunction "VCC_VCC") (pintype "bidirectional"))
      (node (ref "T4") (pin "3") (pinfunction "D_3") (pintype "passive"))
    )
    (net (code "91") (name "Net-(T8-D)") (class "Default")
      (node (ref "R26") (pin "2") (pinfunction "2_2") (pintype "passive"))
      (node (ref "T8") (pin "3") (pinfunction "D_3") (pintype "passive"))
      (node (ref "T9") (pin "1") (pinfunction "G_1") (pintype "passive"))
    )
    (net (code "92") (name "Net-(T9-D)") (class "Default")
      (node (ref "RDA") (pin "5V") (pinfunction "5V_5V") (pintype "bidirectional"))
      (node (ref "T9") (pin "3") (pinfunction "D_3") (pintype "passive"))
    )
    (net (code "93") (name "Net-(ZIO_4-25)") (class "Default")
      (node (ref "LED2") (pin "A") (pinfunction "A_A") (pintype "passive"))
      (node (ref "ZIO_4") (pin "P$13") (pinfunction "25_P$13") (pintype "bidirectional"))
    )
    (net (code "94") (name "Net-(ZIO_4-29)") (class "Default")
      (node (ref "LED1") (pin "A") (pinfunction "A_A") (pintype "passive"))
      (node (ref "ZIO_4") (pin "P$15") (pinfunction "29_P$15") (pintype "bidirectional"))
    )
    (net (code "95") (name "unconnected-(AUDIO_IN-4-Pad3)") (class "Default")
      (node (ref "AUDIO_IN") (pin "3") (pinfunction "4_3") (pintype "bidirectional"))
    )
    (net (code "96") (name "unconnected-(TEMP-CT-Pad10)") (class "Default")
      (node (ref "TEMP") (pin "10") (pinfunction "CT_10") (pintype "input"))
    )
    (net (code "97") (name "unconnected-(TEMP-EP-Pad17)") (class "Default")
      (node (ref "TEMP") (pin "17") (pinfunction "EP_17") (pintype "input"))
    )
    (net (code "98") (name "unconnected-(TEMP-INT-Pad9)") (class "Default")
      (node (ref "TEMP") (pin "9") (pinfunction "INT_9") (pintype "input"))
    )
    (net (code "99") (name "unconnected-(TEMP-Pad5)") (class "Default")
      (node (ref "TEMP") (pin "5") (pinfunction "5_5") (pintype "input"))
    )
    (net (code "100") (name "unconnected-(TEMP-Pad6)") (class "Default")
      (node (ref "TEMP") (pin "6") (pinfunction "6_6") (pintype "input"))
    )
    (net (code "101") (name "unconnected-(TEMP-Pad7)") (class "Default")
      (node (ref "TEMP") (pin "7") (pinfunction "7_7") (pintype "input"))
    )
    (net (code "102") (name "unconnected-(TEMP-Pad8)") (class "Default")
      (node (ref "TEMP") (pin "8") (pinfunction "8_8") (pintype "input"))
    )
    (net (code "103") (name "unconnected-(TEMP-Pad13)") (class "Default")
      (node (ref "TEMP") (pin "13") (pinfunction "13_13") (pintype "input"))
    )
    (net (code "104") (name "unconnected-(TEMP-Pad14)") (class "Default")
      (node (ref "TEMP") (pin "14") (pinfunction "14_14") (pintype "input"))
    )
    (net (code "105") (name "unconnected-(TEMP-Pad15)") (class "Default")
      (node (ref "TEMP") (pin "15") (pinfunction "15_15") (pintype "input"))
    )
    (net (code "106") (name "unconnected-(TEMP-Pad16)") (class "Default")
      (node (ref "TEMP") (pin "16") (pinfunction "16_16") (pintype "input"))
    )
    (net (code "107") (name "unconnected-(ZIO_1-Pad1)") (class "Default")
      (node (ref "ZIO_1") (pin "1") (pinfunction "1_1") (pintype "bidirectional"))
    )
    (net (code "108") (name "unconnected-(ZIO_1-Pad2)") (class "Default")
      (node (ref "ZIO_1") (pin "2") (pinfunction "2_2") (pintype "bidirectional"))
    )
    (net (code "109") (name "unconnected-(ZIO_1-Pad3)") (class "Default")
      (node (ref "ZIO_1") (pin "3") (pinfunction "3_3") (pintype "bidirectional"))
    )
    (net (code "110") (name "unconnected-(ZIO_1-Pad4)") (class "Default")
      (node (ref "ZIO_1") (pin "4") (pinfunction "4_4") (pintype "bidirectional"))
    )
    (net (code "111") (name "unconnected-(ZIO_1-Pad5)") (class "Default")
      (node (ref "ZIO_1") (pin "5") (pinfunction "5_5") (pintype "bidirectional"))
    )
    (net (code "112") (name "unconnected-(ZIO_1-Pad12)") (class "Default")
      (node (ref "ZIO_1") (pin "12") (pinfunction "12_12") (pintype "bidirectional"))
    )
    (net (code "113") (name "unconnected-(ZIO_1-Pad14)") (class "Default")
      (node (ref "ZIO_1") (pin "14") (pinfunction "14_14") (pintype "bidirectional"))
    )
    (net (code "114") (name "unconnected-(ZIO_1-Pad15)") (class "Default")
      (node (ref "ZIO_1") (pin "15") (pinfunction "15_15") (pintype "bidirectional"))
    )
    (net (code "115") (name "unconnected-(ZIO_1-Pad16)") (class "Default")
      (node (ref "ZIO_1") (pin "16") (pinfunction "16_16") (pintype "bidirectional"))
    )
    (net (code "116") (name "unconnected-(ZIO_2-Pad1)") (class "Default")
      (node (ref "ZIO_2") (pin "1") (pinfunction "1_1") (pintype "bidirectional"))
    )
    (net (code "117") (name "unconnected-(ZIO_2-Pad2)") (class "Default")
      (node (ref "ZIO_2") (pin "2") (pinfunction "2_2") (pintype "bidirectional"))
    )
    (net (code "118") (name "unconnected-(ZIO_2-Pad3)") (class "Default")
      (node (ref "ZIO_2") (pin "3") (pinfunction "3_3") (pintype "bidirectional"))
    )
    (net (code "119") (name "unconnected-(ZIO_2-Pad4)") (class "Default")
      (node (ref "ZIO_2") (pin "4") (pinfunction "4_4") (pintype "bidirectional"))
    )
    (net (code "120") (name "unconnected-(ZIO_2-Pad5)") (class "Default")
      (node (ref "ZIO_2") (pin "5") (pinfunction "5_5") (pintype "bidirectional"))
    )
    (net (code "121") (name "unconnected-(ZIO_2-Pad6)") (class "Default")
      (node (ref "ZIO_2") (pin "6") (pinfunction "6_6") (pintype "bidirectional"))
    )
    (net (code "122") (name "unconnected-(ZIO_2-Pad7)") (class "Default")
      (node (ref "ZIO_2") (pin "7") (pinfunction "7_7") (pintype "bidirectional"))
    )
    (net (code "123") (name "unconnected-(ZIO_2-Pad8)") (class "Default")
      (node (ref "ZIO_2") (pin "8") (pinfunction "8_8") (pintype "bidirectional"))
    )
    (net (code "124") (name "unconnected-(ZIO_2-Pad9)") (class "Default")
      (node (ref "ZIO_2") (pin "9") (pinfunction "9_9") (pintype "bidirectional"))
    )
    (net (code "125") (name "unconnected-(ZIO_2-Pad10)") (class "Default")
      (node (ref "ZIO_2") (pin "10") (pinfunction "10_10") (pintype "bidirectional"))
    )
    (net (code "126") (name "unconnected-(ZIO_2-Pad11)") (class "Default")
      (node (ref "ZIO_2") (pin "11") (pinfunction "11_11") (pintype "bidirectional"))
    )
    (net (code "127") (name "unconnected-(ZIO_2-Pad12)") (class "Default")
      (node (ref "ZIO_2") (pin "12") (pinfunction "12_12") (pintype "bidirectional"))
    )
    (net (code "128") (name "unconnected-(ZIO_2-Pad13)") (class "Default")
      (node (ref "ZIO_2") (pin "13") (pinfunction "13_13") (pintype "bidirectional"))
    )
    (net (code "129") (name "unconnected-(ZIO_2-Pad14)") (class "Default")
      (node (ref "ZIO_2") (pin "14") (pinfunction "14_14") (pintype "bidirectional"))
    )
    (net (code "130") (name "unconnected-(ZIO_2-Pad15)") (class "Default")
      (node (ref "ZIO_2") (pin "15") (pinfunction "15_15") (pintype "bidirectional"))
    )
    (net (code "131") (name "unconnected-(ZIO_2-Pad16)") (class "Default")
      (node (ref "ZIO_2") (pin "16") (pinfunction "16_16") (pintype "bidirectional"))
    )
    (net (code "132") (name "unconnected-(ZIO_2-Pad17)") (class "Default")
      (node (ref "ZIO_2") (pin "17") (pinfunction "17_17") (pintype "bidirectional"))
    )
    (net (code "133") (name "unconnected-(ZIO_2-Pad19)") (class "Default")
      (node (ref "ZIO_2") (pin "19") (pinfunction "19_19") (pintype "bidirectional"))
    )
    (net (code "134") (name "unconnected-(ZIO_2-Pad20)") (class "Default")
      (node (ref "ZIO_2") (pin "20") (pinfunction "20_20") (pintype "bidirectional"))
    )
    (net (code "135") (name "unconnected-(ZIO_2-Pad21)") (class "Default")
      (node (ref "ZIO_2") (pin "21") (pinfunction "21_21") (pintype "bidirectional"))
    )
    (net (code "136") (name "unconnected-(ZIO_2-Pad22)") (class "Default")
      (node (ref "ZIO_2") (pin "22") (pinfunction "22_22") (pintype "bidirectional"))
    )
    (net (code "137") (name "unconnected-(ZIO_2-Pad23)") (class "Default")
      (node (ref "ZIO_2") (pin "23") (pinfunction "23_23") (pintype "bidirectional"))
    )
    (net (code "138") (name "unconnected-(ZIO_2-Pad25)") (class "Default")
      (node (ref "ZIO_2") (pin "25") (pinfunction "25_25") (pintype "bidirectional"))
    )
    (net (code "139") (name "unconnected-(ZIO_2-Pad27)") (class "Default")
      (node (ref "ZIO_2") (pin "27") (pinfunction "27_27") (pintype "bidirectional"))
    )
    (net (code "140") (name "unconnected-(ZIO_2-Pad29)") (class "Default")
      (node (ref "ZIO_2") (pin "29") (pinfunction "29_29") (pintype "bidirectional"))
    )
    (net (code "141") (name "unconnected-(ZIO_3-Pad5)") (class "Default")
      (node (ref "ZIO_3") (pin "5") (pinfunction "5_5") (pintype "bidirectional"))
    )
    (net (code "142") (name "unconnected-(ZIO_3-Pad6)") (class "Default")
      (node (ref "ZIO_3") (pin "6") (pinfunction "6_6") (pintype "bidirectional"))
    )
    (net (code "143") (name "unconnected-(ZIO_3-Pad7)") (class "Default")
      (node (ref "ZIO_3") (pin "7") (pinfunction "7_7") (pintype "bidirectional"))
    )
    (net (code "144") (name "unconnected-(ZIO_3-Pad10)") (class "Default")
      (node (ref "ZIO_3") (pin "10") (pinfunction "10_10") (pintype "bidirectional"))
    )
    (net (code "145") (name "unconnected-(ZIO_3-Pad12)") (class "Default")
      (node (ref "ZIO_3") (pin "12") (pinfunction "12_12") (pintype "bidirectional"))
    )
    (net (code "146") (name "unconnected-(ZIO_3-Pad14)") (class "Default")
      (node (ref "ZIO_3") (pin "14") (pinfunction "14_14") (pintype "bidirectional"))
    )
    (net (code "147") (name "unconnected-(ZIO_3-Pad16)") (class "Default")
      (node (ref "ZIO_3") (pin "16") (pinfunction "16_16") (pintype "bidirectional"))
    )
    (net (code "148") (name "unconnected-(ZIO_3-Pad18)") (class "Default")
      (node (ref "ZIO_3") (pin "18") (pinfunction "18_18") (pintype "bidirectional"))
    )
    (net (code "149") (name "unconnected-(ZIO_3-Pad20)") (class "Default")
      (node (ref "ZIO_3") (pin "20") (pinfunction "20_20") (pintype "bidirectional"))
    )
    (net (code "150") (name "unconnected-(ZIO_4-1-PadP$1)") (class "Default")
      (node (ref "ZIO_4") (pin "P$1") (pinfunction "1_P$1") (pintype "bidirectional"))
    )
    (net (code "151") (name "unconnected-(ZIO_4-2-PadP$34)") (class "Default")
      (node (ref "ZIO_4") (pin "P$34") (pinfunction "2_P$34") (pintype "bidirectional"))
    )
    (net (code "152") (name "unconnected-(ZIO_4-3-PadP$2)") (class "Default")
      (node (ref "ZIO_4") (pin "P$2") (pinfunction "3_P$2") (pintype "bidirectional"))
    )
    (net (code "153") (name "unconnected-(ZIO_4-4-PadP$33)") (class "Default")
      (node (ref "ZIO_4") (pin "P$33") (pinfunction "4_P$33") (pintype "bidirectional"))
    )
    (net (code "154") (name "unconnected-(ZIO_4-5-PadP$3)") (class "Default")
      (node (ref "ZIO_4") (pin "P$3") (pinfunction "5_P$3") (pintype "bidirectional"))
    )
    (net (code "155") (name "unconnected-(ZIO_4-6-PadP$32)") (class "Default")
      (node (ref "ZIO_4") (pin "P$32") (pinfunction "6_P$32") (pintype "bidirectional"))
    )
    (net (code "156") (name "unconnected-(ZIO_4-8-PadP$31)") (class "Default")
      (node (ref "ZIO_4") (pin "P$31") (pinfunction "8_P$31") (pintype "bidirectional"))
    )
    (net (code "157") (name "unconnected-(ZIO_4-10-PadP$30)") (class "Default")
      (node (ref "ZIO_4") (pin "P$30") (pinfunction "10_P$30") (pintype "bidirectional"))
    )
    (net (code "158") (name "unconnected-(ZIO_4-12-PadP$29)") (class "Default")
      (node (ref "ZIO_4") (pin "P$29") (pinfunction "12_P$29") (pintype "bidirectional"))
    )
    (net (code "159") (name "unconnected-(ZIO_4-14-PadP$28)") (class "Default")
      (node (ref "ZIO_4") (pin "P$28") (pinfunction "14_P$28") (pintype "bidirectional"))
    )
    (net (code "160") (name "unconnected-(ZIO_4-16-PadP$27)") (class "Default")
      (node (ref "ZIO_4") (pin "P$27") (pinfunction "16_P$27") (pintype "bidirectional"))
    )
    (net (code "161") (name "unconnected-(ZIO_4-17-PadP$9)") (class "Default")
      (node (ref "ZIO_4") (pin "P$9") (pinfunction "17_P$9") (pintype "bidirectional"))
    )
    (net (code "162") (name "unconnected-(ZIO_4-22-PadP$24)") (class "Default")
      (node (ref "ZIO_4") (pin "P$24") (pinfunction "22_P$24") (pintype "bidirectional"))
    )
    (net (code "163") (name "unconnected-(ZIO_4-27-PadP$14)") (class "Default")
      (node (ref "ZIO_4") (pin "P$14") (pinfunction "27_P$14") (pintype "bidirectional"))
    )
    (net (code "164") (name "unconnected-(ZIO_4-31-PadP$16)") (class "Default")
      (node (ref "ZIO_4") (pin "P$16") (pinfunction "31_P$16") (pintype "bidirectional"))
    )
  )
)
